# QSPI_EMMC_MICROSD.net
KiCad netlist of a schematic drawn in Altium Designer
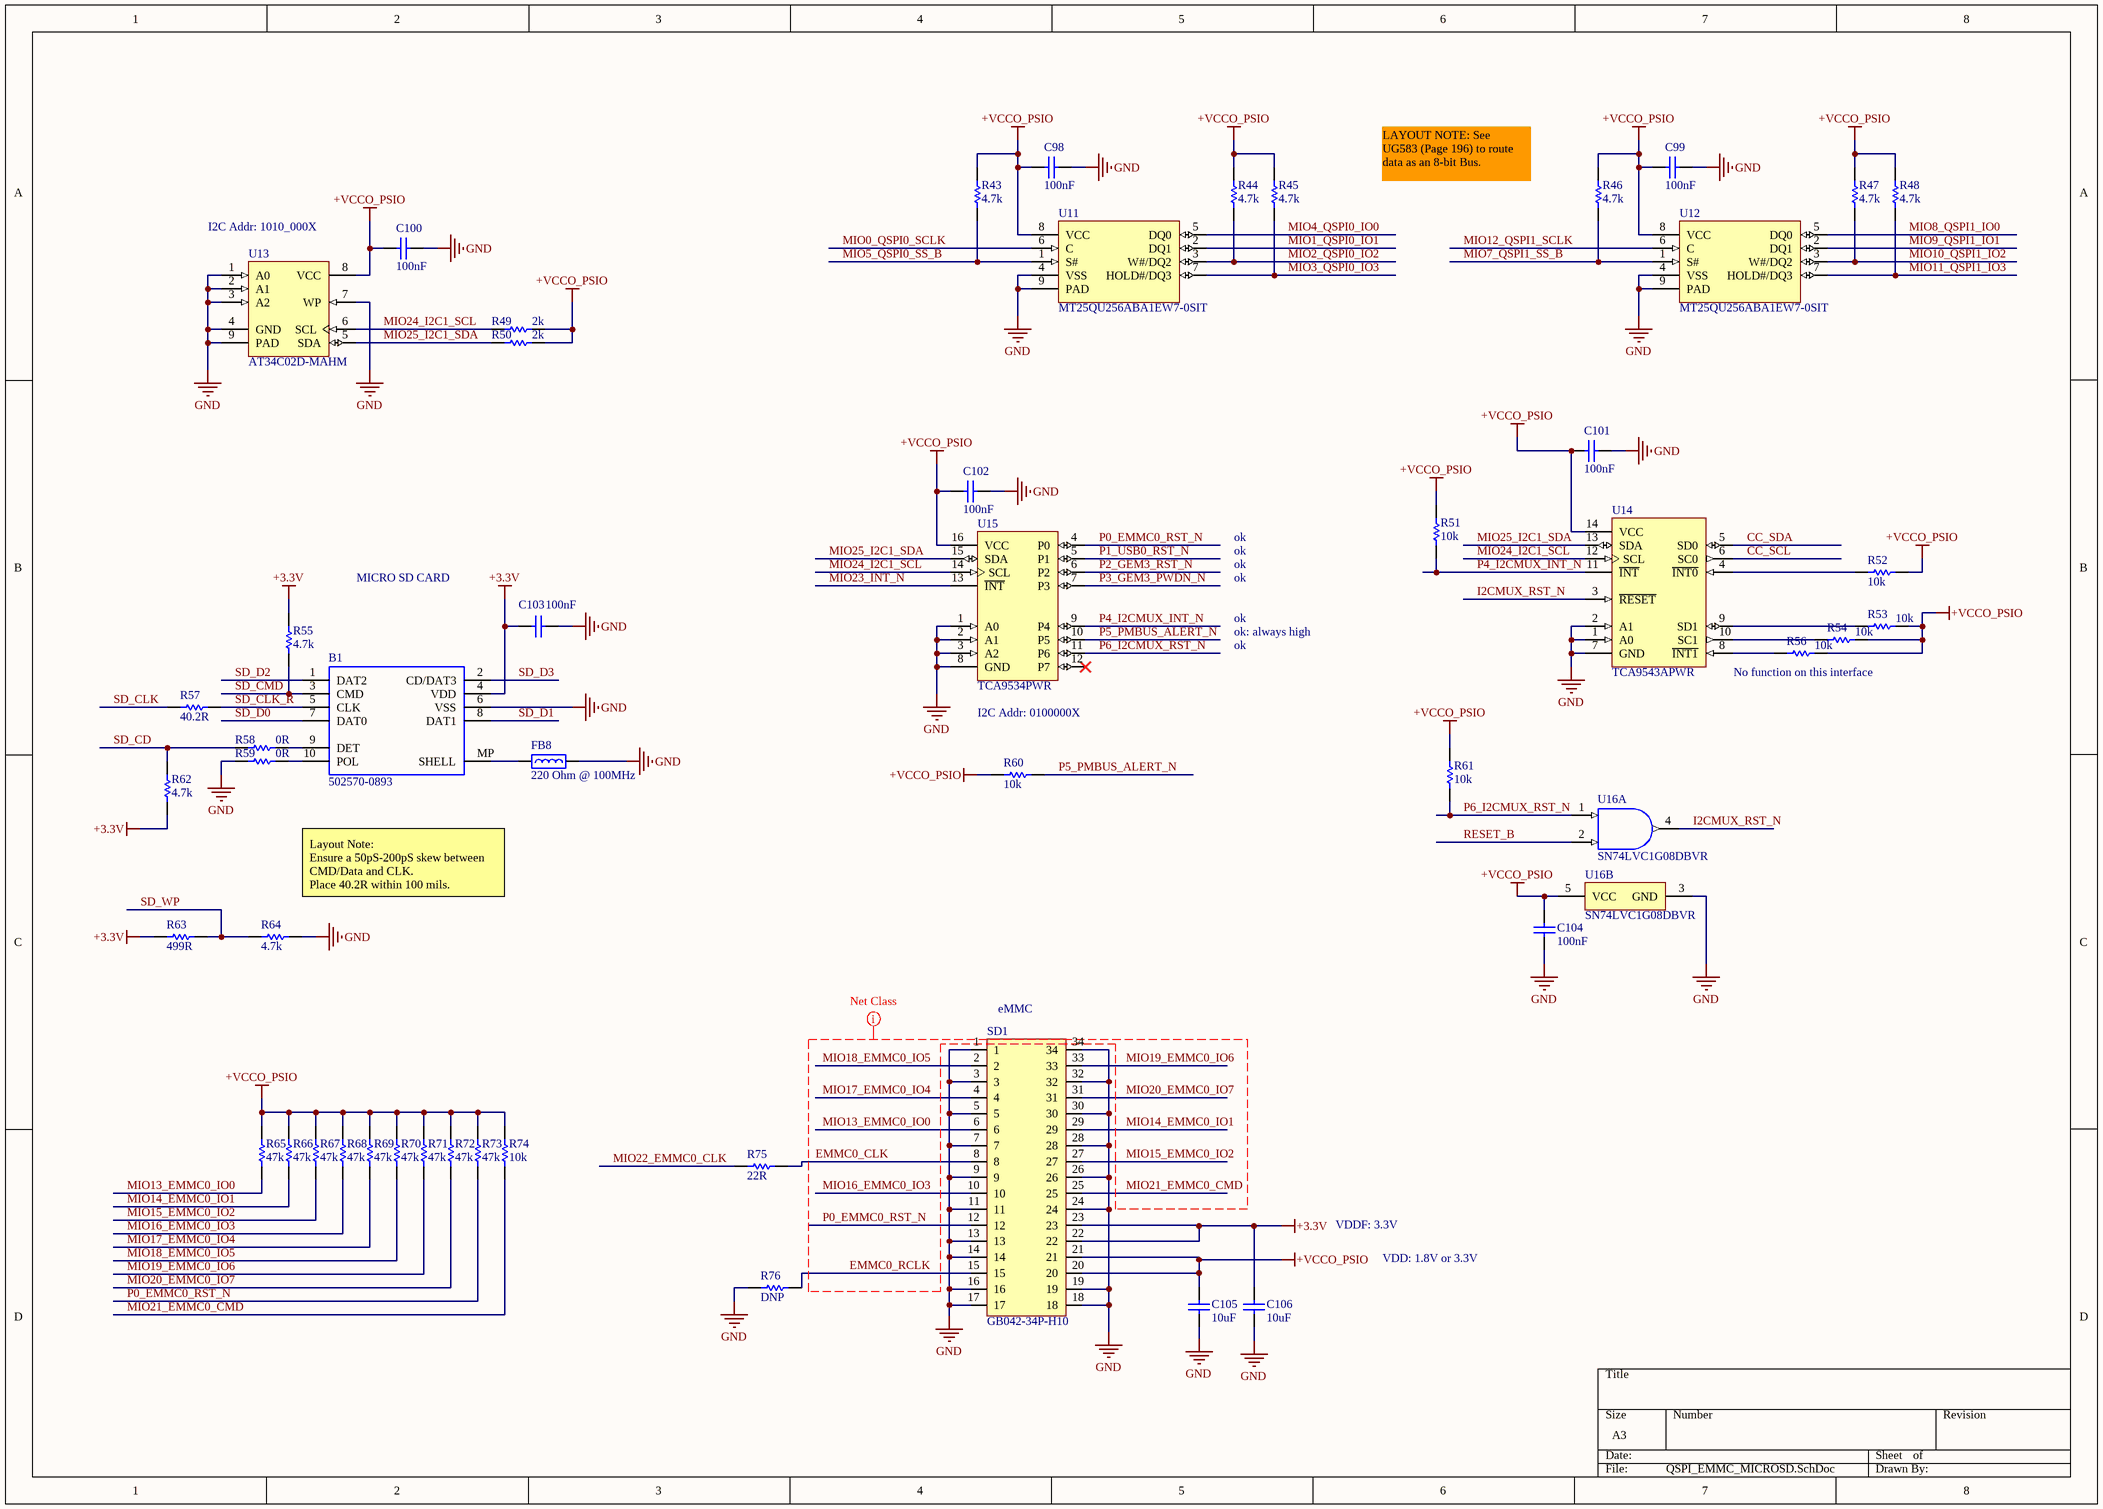
[diagram p0: QSPI_EMMC_MICROSD.SchDoc]

(export (version "E")
  (design (tool "Eeschema 10.0.6"))
  (components
    (comp (ref "B1")
      (value "502570-0893")
      (footprint "502570-0893_1")
      (description "Micro SD card connector,SMT,push-push Micro SD card connector,SMT,push-push")
      (fields (field (name "DIGI-KEY PART NUMBER") "WM19093CT-ND"))
      (libsource (lib "Ultrascale_SchLib") (part "SD 502570-0893"))
    )
    (comp (ref "C98")
      (value "100nF")
      (footprint "CAPC1005L_0402")
      (description "CAP CER 0.1UF 25V X7R 0402")
      (fields (field (name "VOLTAGE") "25V") (field (name "TOLERANCE") "10%"))
      (libsource (lib "Ultrascale_SchLib") (part "CAPCER0402X7R100N25V_10T"))
    )
    (comp (ref "C99")
      (value "100nF")
      (footprint "CAPC1005L_0402")
      (description "CAP CER 0.1UF 25V X7R 0402")
      (fields (field (name "VOLTAGE") "25V") (field (name "TOLERANCE") "10%"))
      (libsource (lib "Ultrascale_SchLib") (part "CAPCER0402X7R100N25V_10T"))
    )
    (comp (ref "C100")
      (value "100nF")
      (footprint "CAPC1005L_0402")
      (description "CAP CER 0.1UF 25V X7R 0402")
      (fields (field (name "VOLTAGE") "25V") (field (name "TOLERANCE") "10%"))
      (libsource (lib "Ultrascale_SchLib") (part "CAPCER0402X7R100N25V_10T"))
    )
    (comp (ref "C101")
      (value "100nF")
      (footprint "CAPC1005L_0402")
      (description "CAP CER 0.1UF 25V X7R 0402")
      (fields (field (name "VOLTAGE") "25V") (field (name "TOLERANCE") "10%"))
      (libsource (lib "Ultrascale_SchLib") (part "CAPCER0402X7R100N25V_10T"))
    )
    (comp (ref "C102")
      (value "100nF")
      (footprint "CAPC1005L_0402")
      (description "CAP CER 0.1UF 25V X7R 0402")
      (fields (field (name "VOLTAGE") "25V") (field (name "TOLERANCE") "10%"))
      (libsource (lib "Ultrascale_SchLib") (part "CAPCER0402X7R100N25V_10T"))
    )
    (comp (ref "C103")
      (value "100nF")
      (footprint "CAPC1005L_0402")
      (description "CAP CER 0.1UF 25V X7R 0402")
      (fields (field (name "VOLTAGE") "25V") (field (name "TOLERANCE") "10%"))
      (libsource (lib "Ultrascale_SchLib") (part "CAPCER0402X7R100N25V_10T"))
    )
    (comp (ref "C104")
      (value "100nF")
      (footprint "CAPC1005L_0402")
      (description "CAP CER 0.1UF 25V X7R 0402")
      (fields (field (name "VOLTAGE") "25V") (field (name "TOLERANCE") "10%"))
      (libsource (lib "Ultrascale_SchLib") (part "CAPCER0402X7R100N25V_10T"))
    )
    (comp (ref "C105")
      (value "10uF")
      (footprint "CAPC1005L_0402")
      (description "CAP CER 10UF 10V X5R 0402")
      (fields (field (name "VOLTAGE") "10V") (field (name "TOLERANCE") "20%"))
      (libsource (lib "Ultrascale_SchLib") (part "CAPCER0402X5R10U10V_20T"))
    )
    (comp (ref "C106")
      (value "10uF")
      (footprint "CAPC1005L_0402")
      (description "CAP CER 10UF 10V X5R 0402")
      (fields (field (name "VOLTAGE") "10V") (field (name "TOLERANCE") "20%"))
      (libsource (lib "Ultrascale_SchLib") (part "CAPCER0402X5R10U10V_20T"))
    )
    (comp (ref "FB8")
      (value "BEAD0603_220_2A5_40M")
      (footprint "INDC1608N_0603")
      (description "FERRITE BEAD 220 OHM 0603 1LN")
      (fields (field (name "IMPEDANCE @ FREQUENCY") "220 Ohm @ 100MHz"))
      (libsource (lib "Ultrascale_SchLib") (part "BEAD0603_220_2A5_40M"))
    )
    (comp (ref "R43")
      (value "4.7k")
      (footprint "RESC1005L_0402")
      (description "RES SMD 4.7K OHM 1% 1/10W 0402")
      (fields (field (name "POWER") "1/10W") (field (name "TOLERANCE") "1%"))
      (libsource (lib "Ultrascale_SchLib") (part "RES0402_4K7_0W1_1T"))
    )
    (comp (ref "R44")
      (value "4.7k")
      (footprint "RESC1005L_0402")
      (description "RES SMD 4.7K OHM 1% 1/10W 0402")
      (fields (field (name "POWER") "1/10W") (field (name "TOLERANCE") "1%"))
      (libsource (lib "Ultrascale_SchLib") (part "RES0402_4K7_0W1_1T"))
    )
    (comp (ref "R45")
      (value "4.7k")
      (footprint "RESC1005L_0402")
      (description "RES SMD 4.7K OHM 1% 1/10W 0402")
      (fields (field (name "POWER") "1/10W") (field (name "TOLERANCE") "1%"))
      (libsource (lib "Ultrascale_SchLib") (part "RES0402_4K7_0W1_1T"))
    )
    (comp (ref "R46")
      (value "4.7k")
      (footprint "RESC1005L_0402")
      (description "RES SMD 4.7K OHM 1% 1/10W 0402")
      (fields (field (name "POWER") "1/10W") (field (name "TOLERANCE") "1%"))
      (libsource (lib "Ultrascale_SchLib") (part "RES0402_4K7_0W1_1T"))
    )
    (comp (ref "R47")
      (value "4.7k")
      (footprint "RESC1005L_0402")
      (description "RES SMD 4.7K OHM 1% 1/10W 0402")
      (fields (field (name "POWER") "1/10W") (field (name "TOLERANCE") "1%"))
      (libsource (lib "Ultrascale_SchLib") (part "RES0402_4K7_0W1_1T"))
    )
    (comp (ref "R48")
      (value "4.7k")
      (footprint "RESC1005L_0402")
      (description "RES SMD 4.7K OHM 1% 1/10W 0402")
      (fields (field (name "POWER") "1/10W") (field (name "TOLERANCE") "1%"))
      (libsource (lib "Ultrascale_SchLib") (part "RES0402_4K7_0W1_1T"))
    )
    (comp (ref "R49")
      (value "2k")
      (footprint "RESC1005L_0402")
      (description "RES SMD 2K OHM 1% 1/16W 0402")
      (fields (field (name "POWER") "1/10W") (field (name "TOLERANCE") "1%"))
      (libsource (lib "Ultrascale_SchLib") (part "RES0402_2K_0W1_1T"))
    )
    (comp (ref "R50")
      (value "2k")
      (footprint "RESC1005L_0402")
      (description "RES SMD 2K OHM 1% 1/16W 0402")
      (fields (field (name "POWER") "1/10W") (field (name "TOLERANCE") "1%"))
      (libsource (lib "Ultrascale_SchLib") (part "RES0402_2K_0W1_1T"))
    )
    (comp (ref "R51")
      (value "10k")
      (footprint "RESC1005L_0402")
      (description "RES SMD 10K OHM 0.5% 1/16W 0402")
      (fields (field (name "POWER") "1/16W") (field (name "TOLERANCE") "0.5%"))
      (libsource (lib "Ultrascale_SchLib") (part "RES0402_10K_0W1_05T"))
    )
    (comp (ref "R52")
      (value "10k")
      (footprint "RESC1005L_0402")
      (description "RES SMD 10K OHM 0.5% 1/16W 0402")
      (fields (field (name "POWER") "1/16W") (field (name "TOLERANCE") "0.5%"))
      (libsource (lib "Ultrascale_SchLib") (part "RES0402_10K_0W1_05T"))
    )
    (comp (ref "R53")
      (value "10k")
      (footprint "RESC1005L_0402")
      (description "RES SMD 10K OHM 0.5% 1/16W 0402")
      (fields (field (name "POWER") "1/16W") (field (name "TOLERANCE") "0.5%"))
      (libsource (lib "Ultrascale_SchLib") (part "RES0402_10K_0W1_05T"))
    )
    (comp (ref "R54")
      (value "10k")
      (footprint "RESC1005L_0402")
      (description "RES SMD 10K OHM 0.5% 1/16W 0402")
      (fields (field (name "POWER") "1/16W") (field (name "TOLERANCE") "0.5%"))
      (libsource (lib "Ultrascale_SchLib") (part "RES0402_10K_0W1_05T"))
    )
    (comp (ref "R55")
      (value "4.7k")
      (footprint "RESC1005L_0402")
      (description "RES SMD 4.7K OHM 1% 1/10W 0402")
      (fields (field (name "POWER") "1/10W") (field (name "TOLERANCE") "1%"))
      (libsource (lib "Ultrascale_SchLib") (part "RES0402_4K7_0W1_1T"))
    )
    (comp (ref "R56")
      (value "10k")
      (footprint "RESC1005L_0402")
      (description "RES SMD 10K OHM 0.5% 1/16W 0402")
      (fields (field (name "POWER") "1/16W") (field (name "TOLERANCE") "0.5%"))
      (libsource (lib "Ultrascale_SchLib") (part "RES0402_10K_0W1_05T"))
    )
    (comp (ref "R57")
      (value "40.2R")
      (footprint "RESC1005L_0402")
      (description "RES SMD 40.2 OHM 1% 1/10W 0402")
      (fields (field (name "POWER") "1/10W") (field (name "TOLERANCE") "1%"))
      (libsource (lib "Ultrascale_SchLib") (part "RES0402_40R2_0W1_1T"))
    )
    (comp (ref "R58")
      (value "0R")
      (footprint "RESC1005L_0402")
      (description "RES SMD 0 OHM JUMPER 1/10W 0402")
      (fields (field (name "POWER") "1/10W") (field (name "Comment") "RES0402_0R_0W1"))
      (libsource (lib "Ultrascale_SchLib") (part "RES0402_0R_0W1"))
    )
    (comp (ref "R59")
      (value "0R")
      (footprint "RESC1005L_0402")
      (description "RES SMD 0 OHM JUMPER 1/10W 0402")
      (fields (field (name "POWER") "1/10W") (field (name "Comment") "RES0402_0R_0W1"))
      (libsource (lib "Ultrascale_SchLib") (part "RES0402_0R_0W1"))
    )
    (comp (ref "R60")
      (value "10k")
      (footprint "RESC1005L_0402")
      (description "RES SMD 10K OHM 0.5% 1/16W 0402")
      (fields (field (name "POWER") "1/16W") (field (name "TOLERANCE") "0.5%"))
      (libsource (lib "Ultrascale_SchLib") (part "RES0402_10K_0W1_05T"))
    )
    (comp (ref "R61")
      (value "10k")
      (footprint "RESC1005L_0402")
      (description "RES SMD 10K OHM 0.5% 1/16W 0402")
      (fields (field (name "POWER") "1/16W") (field (name "TOLERANCE") "0.5%"))
      (libsource (lib "Ultrascale_SchLib") (part "RES0402_10K_0W1_05T"))
    )
    (comp (ref "R62")
      (value "4.7k")
      (footprint "RESC1005L_0402")
      (description "RES SMD 4.7K OHM 1% 1/10W 0402")
      (fields (field (name "POWER") "1/10W") (field (name "TOLERANCE") "1%"))
      (libsource (lib "Ultrascale_SchLib") (part "RES0402_4K7_0W1_1T"))
    )
    (comp (ref "R63")
      (value "499R")
      (footprint "RESC1005L_0402")
      (description "RES SMD 499 OHM 1% 1/16W 0402")
      (fields (field (name "POWER") "1/10W") (field (name "TOLERANCE") "1%"))
      (libsource (lib "Ultrascale_SchLib") (part "RES0402_499R_0W1_1T"))
    )
    (comp (ref "R64")
      (value "4.7k")
      (footprint "RESC1005L_0402")
      (description "RES SMD 4.7K OHM 1% 1/10W 0402")
      (fields (field (name "POWER") "1/10W") (field (name "TOLERANCE") "1%"))
      (libsource (lib "Ultrascale_SchLib") (part "RES0402_4K7_0W1_1T"))
    )
    (comp (ref "R65")
      (value "47k")
      (footprint "RESC1005L_0402")
      (description "RES SMD 47K OHM 1% 1/10W 0402")
      (fields (field (name "POWER") "1/10W") (field (name "TOLERANCE") "1%"))
      (libsource (lib "Ultrascale_SchLib") (part "RES0402_47K_0W1"))
    )
    (comp (ref "R66")
      (value "47k")
      (footprint "RESC1005L_0402")
      (description "RES SMD 47K OHM 1% 1/10W 0402")
      (fields (field (name "POWER") "1/10W") (field (name "TOLERANCE") "1%"))
      (libsource (lib "Ultrascale_SchLib") (part "RES0402_47K_0W1"))
    )
    (comp (ref "R67")
      (value "47k")
      (footprint "RESC1005L_0402")
      (description "RES SMD 47K OHM 1% 1/10W 0402")
      (fields (field (name "POWER") "1/10W") (field (name "TOLERANCE") "1%"))
      (libsource (lib "Ultrascale_SchLib") (part "RES0402_47K_0W1"))
    )
    (comp (ref "R68")
      (value "47k")
      (footprint "RESC1005L_0402")
      (description "RES SMD 47K OHM 1% 1/10W 0402")
      (fields (field (name "POWER") "1/10W") (field (name "TOLERANCE") "1%"))
      (libsource (lib "Ultrascale_SchLib") (part "RES0402_47K_0W1"))
    )
    (comp (ref "R69")
      (value "47k")
      (footprint "RESC1005L_0402")
      (description "RES SMD 47K OHM 1% 1/10W 0402")
      (fields (field (name "POWER") "1/10W") (field (name "TOLERANCE") "1%"))
      (libsource (lib "Ultrascale_SchLib") (part "RES0402_47K_0W1"))
    )
    (comp (ref "R70")
      (value "47k")
      (footprint "RESC1005L_0402")
      (description "RES SMD 47K OHM 1% 1/10W 0402")
      (fields (field (name "POWER") "1/10W") (field (name "TOLERANCE") "1%"))
      (libsource (lib "Ultrascale_SchLib") (part "RES0402_47K_0W1"))
    )
    (comp (ref "R71")
      (value "47k")
      (footprint "RESC1005L_0402")
      (description "RES SMD 47K OHM 1% 1/10W 0402")
      (fields (field (name "POWER") "1/10W") (field (name "TOLERANCE") "1%"))
      (libsource (lib "Ultrascale_SchLib") (part "RES0402_47K_0W1"))
    )
    (comp (ref "R72")
      (value "47k")
      (footprint "RESC1005L_0402")
      (description "RES SMD 47K OHM 1% 1/10W 0402")
      (fields (field (name "POWER") "1/10W") (field (name "TOLERANCE") "1%"))
      (libsource (lib "Ultrascale_SchLib") (part "RES0402_47K_0W1"))
    )
    (comp (ref "R73")
      (value "47k")
      (footprint "RESC1005L_0402")
      (description "RES SMD 47K OHM 1% 1/10W 0402")
      (fields (field (name "POWER") "1/10W") (field (name "TOLERANCE") "1%"))
      (libsource (lib "Ultrascale_SchLib") (part "RES0402_47K_0W1"))
    )
    (comp (ref "R74")
      (value "10k")
      (footprint "RESC1005L_0402")
      (description "RES SMD 10K OHM 0.5% 1/16W 0402")
      (fields (field (name "POWER") "1/16W") (field (name "TOLERANCE") "0.5%"))
      (libsource (lib "Ultrascale_SchLib") (part "RES0402_10K_0W1_05T"))
    )
    (comp (ref "R75")
      (value "22R")
      (footprint "RESC1005L_0402")
      (description "RES SMD 22 OHM 1% 1/10W 0402")
      (fields (field (name "POWER") "1/10W") (field (name "TOLERANCE") "1%"))
      (libsource (lib "Ultrascale_SchLib") (part "RES0402_22R_0W1_1T"))
    )
    (comp (ref "R76")
      (value "DNP")
      (footprint "RESC1005L_0402")
      (description "RES SMD 0402 Footprint")
      (fields (field (name "Comment") "RES0402"))
      (libsource (lib "Ultrascale_SchLib") (part "RES0402"))
    )
    (comp (ref "SD1")
      (value "GB042-34P-H10")
      (footprint "Ultrascale_PcbLib:GB042-34P-H10")
      (description "Connector, eMMC")
      (libsource (lib "Ultrascale_SchLib") (part "GB042-34P-H10"))
    )
    (comp (ref "U11")
      (value "MT25QU256ABA1EW7-0SIT")
      (footprint "W-PDFN-8_6x5mm")
      (description "IC FLASH 256MBIT 108MHZ 8VPDFN")
      (libsource (lib "Ultrascale_SchLib") (part "MT25QU256ABA1EW7-0SIT"))
    )
    (comp (ref "U12")
      (value "MT25QU256ABA1EW7-0SIT")
      (footprint "W-PDFN-8_6x5mm")
      (description "IC FLASH 256MBIT 108MHZ 8VPDFN")
      (libsource (lib "Ultrascale_SchLib") (part "MT25QU256ABA1EW7-0SIT"))
    )
    (comp (ref "U13")
      (value "AT34C02D-MAHM")
      (footprint "UDFN_9")
      (description "IC EEPROM 2KBIT 1MHZ 8UDFN")
      (libsource (lib "Ultrascale_SchLib") (part "AT34C02D-MAHM"))
    )
    (comp (ref "U14")
      (value "TCA9543APWR")
      (footprint "TSOP_PW14_L")
      (description "IC I2C SW 2CH W/RESET 14TSSOP")
      (libsource (lib "Ultrascale_SchLib") (part "TCA9543APWR"))
    )
    (comp (ref "U15")
      (value "TCA9534PWR")
      (footprint "TSOP_PW16_L")
      (description "IC I/O EXPANDER I2C 8B 16TSSOP")
      (libsource (lib "Ultrascale_SchLib") (part "TCA9534PWR"))
    )
    (comp (ref "U16")
      (value "SN74LVC1G08DBVR")
      (footprint "DBV0005A_N")
      (description "Single 2-Input Positive-AND Gate, DBV0005A, LARGE T&R")
      (fields (field (name "GENERIC PART NUMBER") "SN74LVC1G08"))
      (libsource (lib "Ultrascale_SchLib") (part "SN74LVC1G08DBVR"))
    )
  )
  (nets
    (net (code "1") (name "+3.3V") (class "Default")
      (node (ref "B1") (pin "4") (pinfunction "VDD_4") (pintype "passive"))
      (node (ref "C103") (pin "1") (pinfunction "1_1") (pintype "passive"))
      (node (ref "C106") (pin "2") (pinfunction "2_2") (pintype "passive"))
      (node (ref "R55") (pin "2") (pinfunction "2_2") (pintype "passive"))
      (node (ref "R62") (pin "2") (pinfunction "2_2") (pintype "passive"))
      (node (ref "R63") (pin "1") (pinfunction "1_1") (pintype "passive"))
      (node (ref "SD1") (pin "22") (pinfunction "22_22") (pintype "passive"))
      (node (ref "SD1") (pin "23") (pinfunction "23_23") (pintype "passive"))
    )
    (net (code "2") (name "+VCCO_PSIO") (class "Default")
      (node (ref "C100") (pin "1") (pinfunction "1_1") (pintype "passive"))
      (node (ref "C101") (pin "2") (pinfunction "2_2") (pintype "passive"))
      (node (ref "C102") (pin "1") (pinfunction "1_1") (pintype "passive"))
      (node (ref "C104") (pin "1") (pinfunction "1_1") (pintype "passive"))
      (node (ref "C105") (pin "2") (pinfunction "2_2") (pintype "passive"))
      (node (ref "C98") (pin "1") (pinfunction "1_1") (pintype "passive"))
      (node (ref "C99") (pin "1") (pinfunction "1_1") (pintype "passive"))
      (node (ref "R43") (pin "1") (pinfunction "1_1") (pintype "passive"))
      (node (ref "R44") (pin "1") (pinfunction "1_1") (pintype "passive"))
      (node (ref "R45") (pin "1") (pinfunction "1_1") (pintype "passive"))
      (node (ref "R46") (pin "1") (pinfunction "1_1") (pintype "passive"))
      (node (ref "R47") (pin "1") (pinfunction "1_1") (pintype "passive"))
      (node (ref "R48") (pin "1") (pinfunction "1_1") (pintype "passive"))
      (node (ref "R49") (pin "2") (pinfunction "2_2") (pintype "passive"))
      (node (ref "R50") (pin "2") (pinfunction "2_2") (pintype "passive"))
      (node (ref "R51") (pin "1") (pinfunction "1_1") (pintype "passive"))
      (node (ref "R52") (pin "1") (pinfunction "1_1") (pintype "passive"))
      (node (ref "R53") (pin "1") (pinfunction "1_1") (pintype "passive"))
      (node (ref "R54") (pin "1") (pinfunction "1_1") (pintype "passive"))
      (node (ref "R56") (pin "1") (pinfunction "1_1") (pintype "passive"))
      (node (ref "R60") (pin "1") (pinfunction "1_1") (pintype "passive"))
      (node (ref "R61") (pin "2") (pinfunction "2_2") (pintype "passive"))
      (node (ref "R65") (pin "2") (pinfunction "2_2") (pintype "passive"))
      (node (ref "R66") (pin "2") (pinfunction "2_2") (pintype "passive"))
      (node (ref "R67") (pin "2") (pinfunction "2_2") (pintype "passive"))
      (node (ref "R68") (pin "2") (pinfunction "2_2") (pintype "passive"))
      (node (ref "R69") (pin "2") (pinfunction "2_2") (pintype "passive"))
      (node (ref "R70") (pin "2") (pinfunction "2_2") (pintype "passive"))
      (node (ref "R71") (pin "2") (pinfunction "2_2") (pintype "passive"))
      (node (ref "R72") (pin "2") (pinfunction "2_2") (pintype "passive"))
      (node (ref "R73") (pin "2") (pinfunction "2_2") (pintype "passive"))
      (node (ref "R74") (pin "2") (pinfunction "2_2") (pintype "passive"))
      (node (ref "SD1") (pin "20") (pinfunction "20_20") (pintype "passive"))
      (node (ref "SD1") (pin "21") (pinfunction "21_21") (pintype "passive"))
      (node (ref "U11") (pin "8") (pinfunction "VCC_8") (pintype "passive"))
      (node (ref "U12") (pin "8") (pinfunction "VCC_8") (pintype "passive"))
      (node (ref "U13") (pin "8") (pinfunction "VCC_8") (pintype "power_in"))
      (node (ref "U14") (pin "14") (pinfunction "VCC_14") (pintype "power_in"))
      (node (ref "U15") (pin "16") (pinfunction "VCC_16") (pintype "power_in"))
      (node (ref "U16") (pin "5") (pinfunction "VCC_5") (pintype "power_in"))
    )
    (net (code "3") (name "/CC_SCL") (class "Default")
      (node (ref "U14") (pin "6") (pinfunction "SC0_6") (pintype "output"))
    )
    (net (code "4") (name "/CC_SDA") (class "Default")
      (node (ref "U14") (pin "5") (pinfunction "SD0_5") (pintype "bidirectional"))
    )
    (net (code "5") (name "/EMMC0_CLK") (class "Default")
      (node (ref "R75") (pin "2") (pinfunction "2_2") (pintype "passive"))
      (node (ref "SD1") (pin "8") (pinfunction "8_8") (pintype "passive"))
    )
    (net (code "6") (name "/EMMC0_RCLK") (class "Default")
      (node (ref "R76") (pin "2") (pinfunction "2_2") (pintype "passive"))
      (node (ref "SD1") (pin "15") (pinfunction "15_15") (pintype "passive"))
    )
    (net (code "7") (name "/I2CMUX_RST_N") (class "Default")
      (node (ref "U14") (pin "3") (pinfunction "~{RESET}_3") (pintype "input"))
      (node (ref "U16") (pin "4") (pinfunction "Y_4") (pintype "output"))
    )
    (net (code "8") (name "/MIO0_QSPI0_SCLK") (class "Default")
      (node (ref "U11") (pin "6") (pinfunction "C_6") (pintype "input"))
    )
    (net (code "9") (name "/MIO1_QSPI0_IO1") (class "Default")
      (node (ref "U11") (pin "2") (pinfunction "DQ1_2") (pintype "bidirectional"))
    )
    (net (code "10") (name "/MIO2_QSPI0_IO2") (class "Default")
      (node (ref "R44") (pin "2") (pinfunction "2_2") (pintype "passive"))
      (node (ref "U11") (pin "3") (pinfunction "W#/DQ2_3") (pintype "bidirectional"))
    )
    (net (code "11") (name "/MIO3_QSPI0_IO3") (class "Default")
      (node (ref "R45") (pin "2") (pinfunction "2_2") (pintype "passive"))
      (node (ref "U11") (pin "7") (pinfunction "HOLD#/DQ3_7") (pintype "bidirectional"))
    )
    (net (code "12") (name "/MIO4_QSPI0_IO0") (class "Default")
      (node (ref "U11") (pin "5") (pinfunction "DQ0_5") (pintype "bidirectional"))
    )
    (net (code "13") (name "/MIO5_QSPI0_SS_B") (class "Default")
      (node (ref "R43") (pin "2") (pinfunction "2_2") (pintype "passive"))
      (node (ref "U11") (pin "1") (pinfunction "S#_1") (pintype "input"))
    )
    (net (code "14") (name "/MIO7_QSPI1_SS_B") (class "Default")
      (node (ref "R46") (pin "2") (pinfunction "2_2") (pintype "passive"))
      (node (ref "U12") (pin "1") (pinfunction "S#_1") (pintype "input"))
    )
    (net (code "15") (name "/MIO8_QSPI1_IO0") (class "Default")
      (node (ref "U12") (pin "5") (pinfunction "DQ0_5") (pintype "bidirectional"))
    )
    (net (code "16") (name "/MIO9_QSPI1_IO1") (class "Default")
      (node (ref "U12") (pin "2") (pinfunction "DQ1_2") (pintype "bidirectional"))
    )
    (net (code "17") (name "/MIO10_QSPI1_IO2") (class "Default")
      (node (ref "R47") (pin "2") (pinfunction "2_2") (pintype "passive"))
      (node (ref "U12") (pin "3") (pinfunction "W#/DQ2_3") (pintype "bidirectional"))
    )
    (net (code "18") (name "/MIO11_QSPI1_IO3") (class "Default")
      (node (ref "R48") (pin "2") (pinfunction "2_2") (pintype "passive"))
      (node (ref "U12") (pin "7") (pinfunction "HOLD#/DQ3_7") (pintype "bidirectional"))
    )
    (net (code "19") (name "/MIO12_QSPI1_SCLK") (class "Default")
      (node (ref "U12") (pin "6") (pinfunction "C_6") (pintype "input"))
    )
    (net (code "20") (name "/MIO13_EMMC0_IO0") (class "Default")
      (node (ref "R65") (pin "1") (pinfunction "1_1") (pintype "passive"))
      (node (ref "SD1") (pin "6") (pinfunction "6_6") (pintype "passive"))
    )
    (net (code "21") (name "/MIO14_EMMC0_IO1") (class "Default")
      (node (ref "R66") (pin "1") (pinfunction "1_1") (pintype "passive"))
      (node (ref "SD1") (pin "29") (pinfunction "29_29") (pintype "passive"))
    )
    (net (code "22") (name "/MIO15_EMMC0_IO2") (class "Default")
      (node (ref "R67") (pin "1") (pinfunction "1_1") (pintype "passive"))
      (node (ref "SD1") (pin "27") (pinfunction "27_27") (pintype "passive"))
    )
    (net (code "23") (name "/MIO16_EMMC0_IO3") (class "Default")
      (node (ref "R68") (pin "1") (pinfunction "1_1") (pintype "passive"))
      (node (ref "SD1") (pin "10") (pinfunction "10_10") (pintype "passive"))
    )
    (net (code "24") (name "/MIO17_EMMC0_IO4") (class "Default")
      (node (ref "R69") (pin "1") (pinfunction "1_1") (pintype "passive"))
      (node (ref "SD1") (pin "4") (pinfunction "4_4") (pintype "passive"))
    )
    (net (code "25") (name "/MIO18_EMMC0_IO5") (class "Default")
      (node (ref "R70") (pin "1") (pinfunction "1_1") (pintype "passive"))
      (node (ref "SD1") (pin "2") (pinfunction "2_2") (pintype "passive"))
    )
    (net (code "26") (name "/MIO19_EMMC0_IO6") (class "Default")
      (node (ref "R71") (pin "1") (pinfunction "1_1") (pintype "passive"))
      (node (ref "SD1") (pin "33") (pinfunction "33_33") (pintype "passive"))
    )
    (net (code "27") (name "/MIO20_EMMC0_IO7") (class "Default")
      (node (ref "R72") (pin "1") (pinfunction "1_1") (pintype "passive"))
      (node (ref "SD1") (pin "31") (pinfunction "31_31") (pintype "passive"))
    )
    (net (code "28") (name "/MIO21_EMMC0_CMD") (class "Default")
      (node (ref "R74") (pin "1") (pinfunction "1_1") (pintype "passive"))
      (node (ref "SD1") (pin "25") (pinfunction "25_25") (pintype "passive"))
    )
    (net (code "29") (name "/MIO22_EMMC0_CLK") (class "Default")
      (node (ref "R75") (pin "1") (pinfunction "1_1") (pintype "passive"))
    )
    (net (code "30") (name "/MIO23_INT_N") (class "Default")
      (node (ref "U15") (pin "13") (pinfunction "~{INT}_13") (pintype "open_collector"))
    )
    (net (code "31") (name "/MIO24_I2C1_SCL") (class "Default")
      (node (ref "R49") (pin "1") (pinfunction "1_1") (pintype "passive"))
      (node (ref "U13") (pin "6") (pinfunction "SCL_6") (pintype "input"))
      (node (ref "U14") (pin "12") (pinfunction "SCL_12") (pintype "input"))
      (node (ref "U15") (pin "14") (pinfunction "SCL_14") (pintype "input"))
    )
    (net (code "32") (name "/MIO25_I2C1_SDA") (class "Default")
      (node (ref "R50") (pin "1") (pinfunction "1_1") (pintype "passive"))
      (node (ref "U13") (pin "5") (pinfunction "SDA_5") (pintype "bidirectional"))
      (node (ref "U14") (pin "13") (pinfunction "SDA_13") (pintype "bidirectional"))
      (node (ref "U15") (pin "15") (pinfunction "SDA_15") (pintype "bidirectional"))
    )
    (net (code "33") (name "/P0_EMMC0_RST_N") (class "Default")
      (node (ref "R73") (pin "1") (pinfunction "1_1") (pintype "passive"))
      (node (ref "SD1") (pin "12") (pinfunction "12_12") (pintype "passive"))
      (node (ref "U15") (pin "4") (pinfunction "P0_4") (pintype "bidirectional"))
    )
    (net (code "34") (name "/P1_USB0_RST_N") (class "Default")
      (node (ref "U15") (pin "5") (pinfunction "P1_5") (pintype "bidirectional"))
    )
    (net (code "35") (name "/P2_GEM3_RST_N") (class "Default")
      (node (ref "U15") (pin "6") (pinfunction "P2_6") (pintype "bidirectional"))
    )
    (net (code "36") (name "/P3_GEM3_PWDN_N") (class "Default")
      (node (ref "U15") (pin "7") (pinfunction "P3_7") (pintype "bidirectional"))
    )
    (net (code "37") (name "/P4_I2CMUX_INT_N") (class "Default")
      (node (ref "R51") (pin "2") (pinfunction "2_2") (pintype "passive"))
      (node (ref "U14") (pin "11") (pinfunction "~{INT}_11") (pintype "open_collector"))
      (node (ref "U15") (pin "9") (pinfunction "P4_9") (pintype "bidirectional"))
    )
    (net (code "38") (name "/P5_PMBUS_ALERT_N") (class "Default")
      (node (ref "R60") (pin "2") (pinfunction "2_2") (pintype "passive"))
      (node (ref "U15") (pin "10") (pinfunction "P5_10") (pintype "bidirectional"))
    )
    (net (code "39") (name "/P6_I2CMUX_RST_N") (class "Default")
      (node (ref "R61") (pin "1") (pinfunction "1_1") (pintype "passive"))
      (node (ref "U15") (pin "11") (pinfunction "P6_11") (pintype "bidirectional"))
      (node (ref "U16") (pin "1") (pinfunction "A_1") (pintype "input"))
    )
    (net (code "40") (name "/RESET_B") (class "Default")
      (node (ref "U16") (pin "2") (pinfunction "B_2") (pintype "input"))
    )
    (net (code "41") (name "/SD_CD") (class "Default")
      (node (ref "R58") (pin "2") (pinfunction "2_2") (pintype "passive"))
      (node (ref "R62") (pin "1") (pinfunction "1_1") (pintype "passive"))
    )
    (net (code "42") (name "/SD_CLK") (class "Default")
      (node (ref "R57") (pin "1") (pinfunction "1_1") (pintype "passive"))
    )
    (net (code "43") (name "/SD_CLK_R") (class "Default")
      (node (ref "B1") (pin "5") (pinfunction "CLK_5") (pintype "passive"))
      (node (ref "R57") (pin "2") (pinfunction "2_2") (pintype "passive"))
    )
    (net (code "44") (name "/SD_CMD") (class "Default")
      (node (ref "B1") (pin "3") (pinfunction "CMD_3") (pintype "passive"))
      (node (ref "R55") (pin "1") (pinfunction "1_1") (pintype "passive"))
    )
    (net (code "45") (name "/SD_D0") (class "Default")
      (node (ref "B1") (pin "7") (pinfunction "DAT0_7") (pintype "passive"))
    )
    (net (code "46") (name "/SD_D1") (class "Default")
      (node (ref "B1") (pin "8") (pinfunction "DAT1_8") (pintype "passive"))
    )
    (net (code "47") (name "/SD_D2") (class "Default")
      (node (ref "B1") (pin "1") (pinfunction "DAT2_1") (pintype "passive"))
    )
    (net (code "48") (name "/SD_D3") (class "Default")
      (node (ref "B1") (pin "2") (pinfunction "CD/DAT3_2") (pintype "passive"))
    )
    (net (code "49") (name "/SD_WP") (class "Default")
      (node (ref "R63") (pin "2") (pinfunction "2_2") (pintype "passive"))
      (node (ref "R64") (pin "2") (pinfunction "2_2") (pintype "passive"))
    )
    (net (code "50") (name "GND") (class "Default")
      (node (ref "B1") (pin "6") (pinfunction "VSS_6") (pintype "passive"))
      (node (ref "C100") (pin "2") (pinfunction "2_2") (pintype "passive"))
      (node (ref "C101") (pin "1") (pinfunction "1_1") (pintype "passive"))
      (node (ref "C102") (pin "2") (pinfunction "2_2") (pintype "passive"))
      (node (ref "C103") (pin "2") (pinfunction "2_2") (pintype "passive"))
      (node (ref "C104") (pin "2") (pinfunction "2_2") (pintype "passive"))
      (node (ref "C105") (pin "1") (pinfunction "1_1") (pintype "passive"))
      (node (ref "C106") (pin "1") (pinfunction "1_1") (pintype "passive"))
      (node (ref "C98") (pin "2") (pinfunction "2_2") (pintype "passive"))
      (node (ref "C99") (pin "2") (pinfunction "2_2") (pintype "passive"))
      (node (ref "FB8") (pin "2") (pinfunction "2_2") (pintype "passive"))
      (node (ref "R59") (pin "2") (pinfunction "2_2") (pintype "passive"))
      (node (ref "R64") (pin "1") (pinfunction "1_1") (pintype "passive"))
      (node (ref "R76") (pin "1") (pinfunction "1_1") (pintype "passive"))
      (node (ref "SD1") (pin "1") (pinfunction "1_1") (pintype "passive"))
      (node (ref "SD1") (pin "11") (pinfunction "11_11") (pintype "passive"))
      (node (ref "SD1") (pin "13") (pinfunction "13_13") (pintype "passive"))
      (node (ref "SD1") (pin "14") (pinfunction "14_14") (pintype "passive"))
      (node (ref "SD1") (pin "16") (pinfunction "16_16") (pintype "passive"))
      (node (ref "SD1") (pin "17") (pinfunction "17_17") (pintype "passive"))
      (node (ref "SD1") (pin "18") (pinfunction "18_18") (pintype "passive"))
      (node (ref "SD1") (pin "19") (pinfunction "19_19") (pintype "passive"))
      (node (ref "SD1") (pin "24") (pinfunction "24_24") (pintype "passive"))
      (node (ref "SD1") (pin "26") (pinfunction "26_26") (pintype "passive"))
      (node (ref "SD1") (pin "28") (pinfunction "28_28") (pintype "passive"))
      (node (ref "SD1") (pin "3") (pinfunction "3_3") (pintype "passive"))
      (node (ref "SD1") (pin "30") (pinfunction "30_30") (pintype "passive"))
      (node (ref "SD1") (pin "32") (pinfunction "32_32") (pintype "passive"))
      (node (ref "SD1") (pin "34") (pinfunction "34_34") (pintype "passive"))
      (node (ref "SD1") (pin "5") (pinfunction "5_5") (pintype "passive"))
      (node (ref "SD1") (pin "7") (pinfunction "7_7") (pintype "passive"))
      (node (ref "SD1") (pin "9") (pinfunction "9_9") (pintype "passive"))
      (node (ref "U11") (pin "4") (pinfunction "VSS_4") (pintype "passive"))
      (node (ref "U11") (pin "9") (pinfunction "PAD_9") (pintype "passive"))
      (node (ref "U12") (pin "4") (pinfunction "VSS_4") (pintype "passive"))
      (node (ref "U12") (pin "9") (pinfunction "PAD_9") (pintype "passive"))
      (node (ref "U13") (pin "1") (pinfunction "A0_1") (pintype "input"))
      (node (ref "U13") (pin "2") (pinfunction "A1_2") (pintype "input"))
      (node (ref "U13") (pin "3") (pinfunction "A2_3") (pintype "input"))
      (node (ref "U13") (pin "4") (pinfunction "GND_4") (pintype "power_in"))
      (node (ref "U13") (pin "7") (pinfunction "WP_7") (pintype "input"))
      (node (ref "U13") (pin "9") (pinfunction "PAD_9") (pintype "power_in"))
      (node (ref "U14") (pin "1") (pinfunction "A0_1") (pintype "input"))
      (node (ref "U14") (pin "2") (pinfunction "A1_2") (pintype "input"))
      (node (ref "U14") (pin "7") (pinfunction "GND_7") (pintype "power_in"))
      (node (ref "U15") (pin "1") (pinfunction "A0_1") (pintype "input"))
      (node (ref "U15") (pin "2") (pinfunction "A1_2") (pintype "input"))
      (node (ref "U15") (pin "3") (pinfunction "A2_3") (pintype "input"))
      (node (ref "U15") (pin "8") (pinfunction "GND_8") (pintype "power_in"))
      (node (ref "U16") (pin "3") (pinfunction "GND_3") (pintype "power_in"))
    )
    (net (code "51") (name "Net-(B1-DET)") (class "Default")
      (node (ref "B1") (pin "9") (pinfunction "DET_9") (pintype "passive"))
      (node (ref "R58") (pin "1") (pinfunction "1_1") (pintype "passive"))
    )
    (net (code "52") (name "Net-(B1-POL)") (class "Default")
      (node (ref "B1") (pin "10") (pinfunction "POL_10") (pintype "passive"))
      (node (ref "R59") (pin "1") (pinfunction "1_1") (pintype "passive"))
    )
    (net (code "53") (name "Net-(B1-SHELL)") (class "Default")
      (node (ref "B1") (pin "MP") (pinfunction "SHELL_MP") (pintype "passive"))
      (node (ref "FB8") (pin "1") (pinfunction "1_1") (pintype "passive"))
    )
    (net (code "54") (name "Net-(U14-SC1)") (class "Default")
      (node (ref "R54") (pin "2") (pinfunction "2_2") (pintype "passive"))
      (node (ref "U14") (pin "10") (pinfunction "SC1_10") (pintype "output"))
    )
    (net (code "55") (name "Net-(U14-SD1)") (class "Default")
      (node (ref "R53") (pin "2") (pinfunction "2_2") (pintype "passive"))
      (node (ref "U14") (pin "9") (pinfunction "SD1_9") (pintype "bidirectional"))
    )
    (net (code "56") (name "Net-(U14-~{INT0})") (class "Default")
      (node (ref "R52") (pin "2") (pinfunction "2_2") (pintype "passive"))
      (node (ref "U14") (pin "4") (pinfunction "~{INT0}_4") (pintype "input"))
    )
    (net (code "57") (name "Net-(U14-~{INT1})") (class "Default")
      (node (ref "R56") (pin "2") (pinfunction "2_2") (pintype "passive"))
      (node (ref "U14") (pin "8") (pinfunction "~{INT1}_8") (pintype "input"))
    )
    (net (code "58") (name "unconnected-(U15-P7-Pad12)") (class "Default")
      (node (ref "U15") (pin "12") (pinfunction "P7_12") (pintype "bidirectional+no_connect"))
    )
  )
)
